# magnetorquer_board.net
KiCad netlist of a schematic drawn in EAGLE
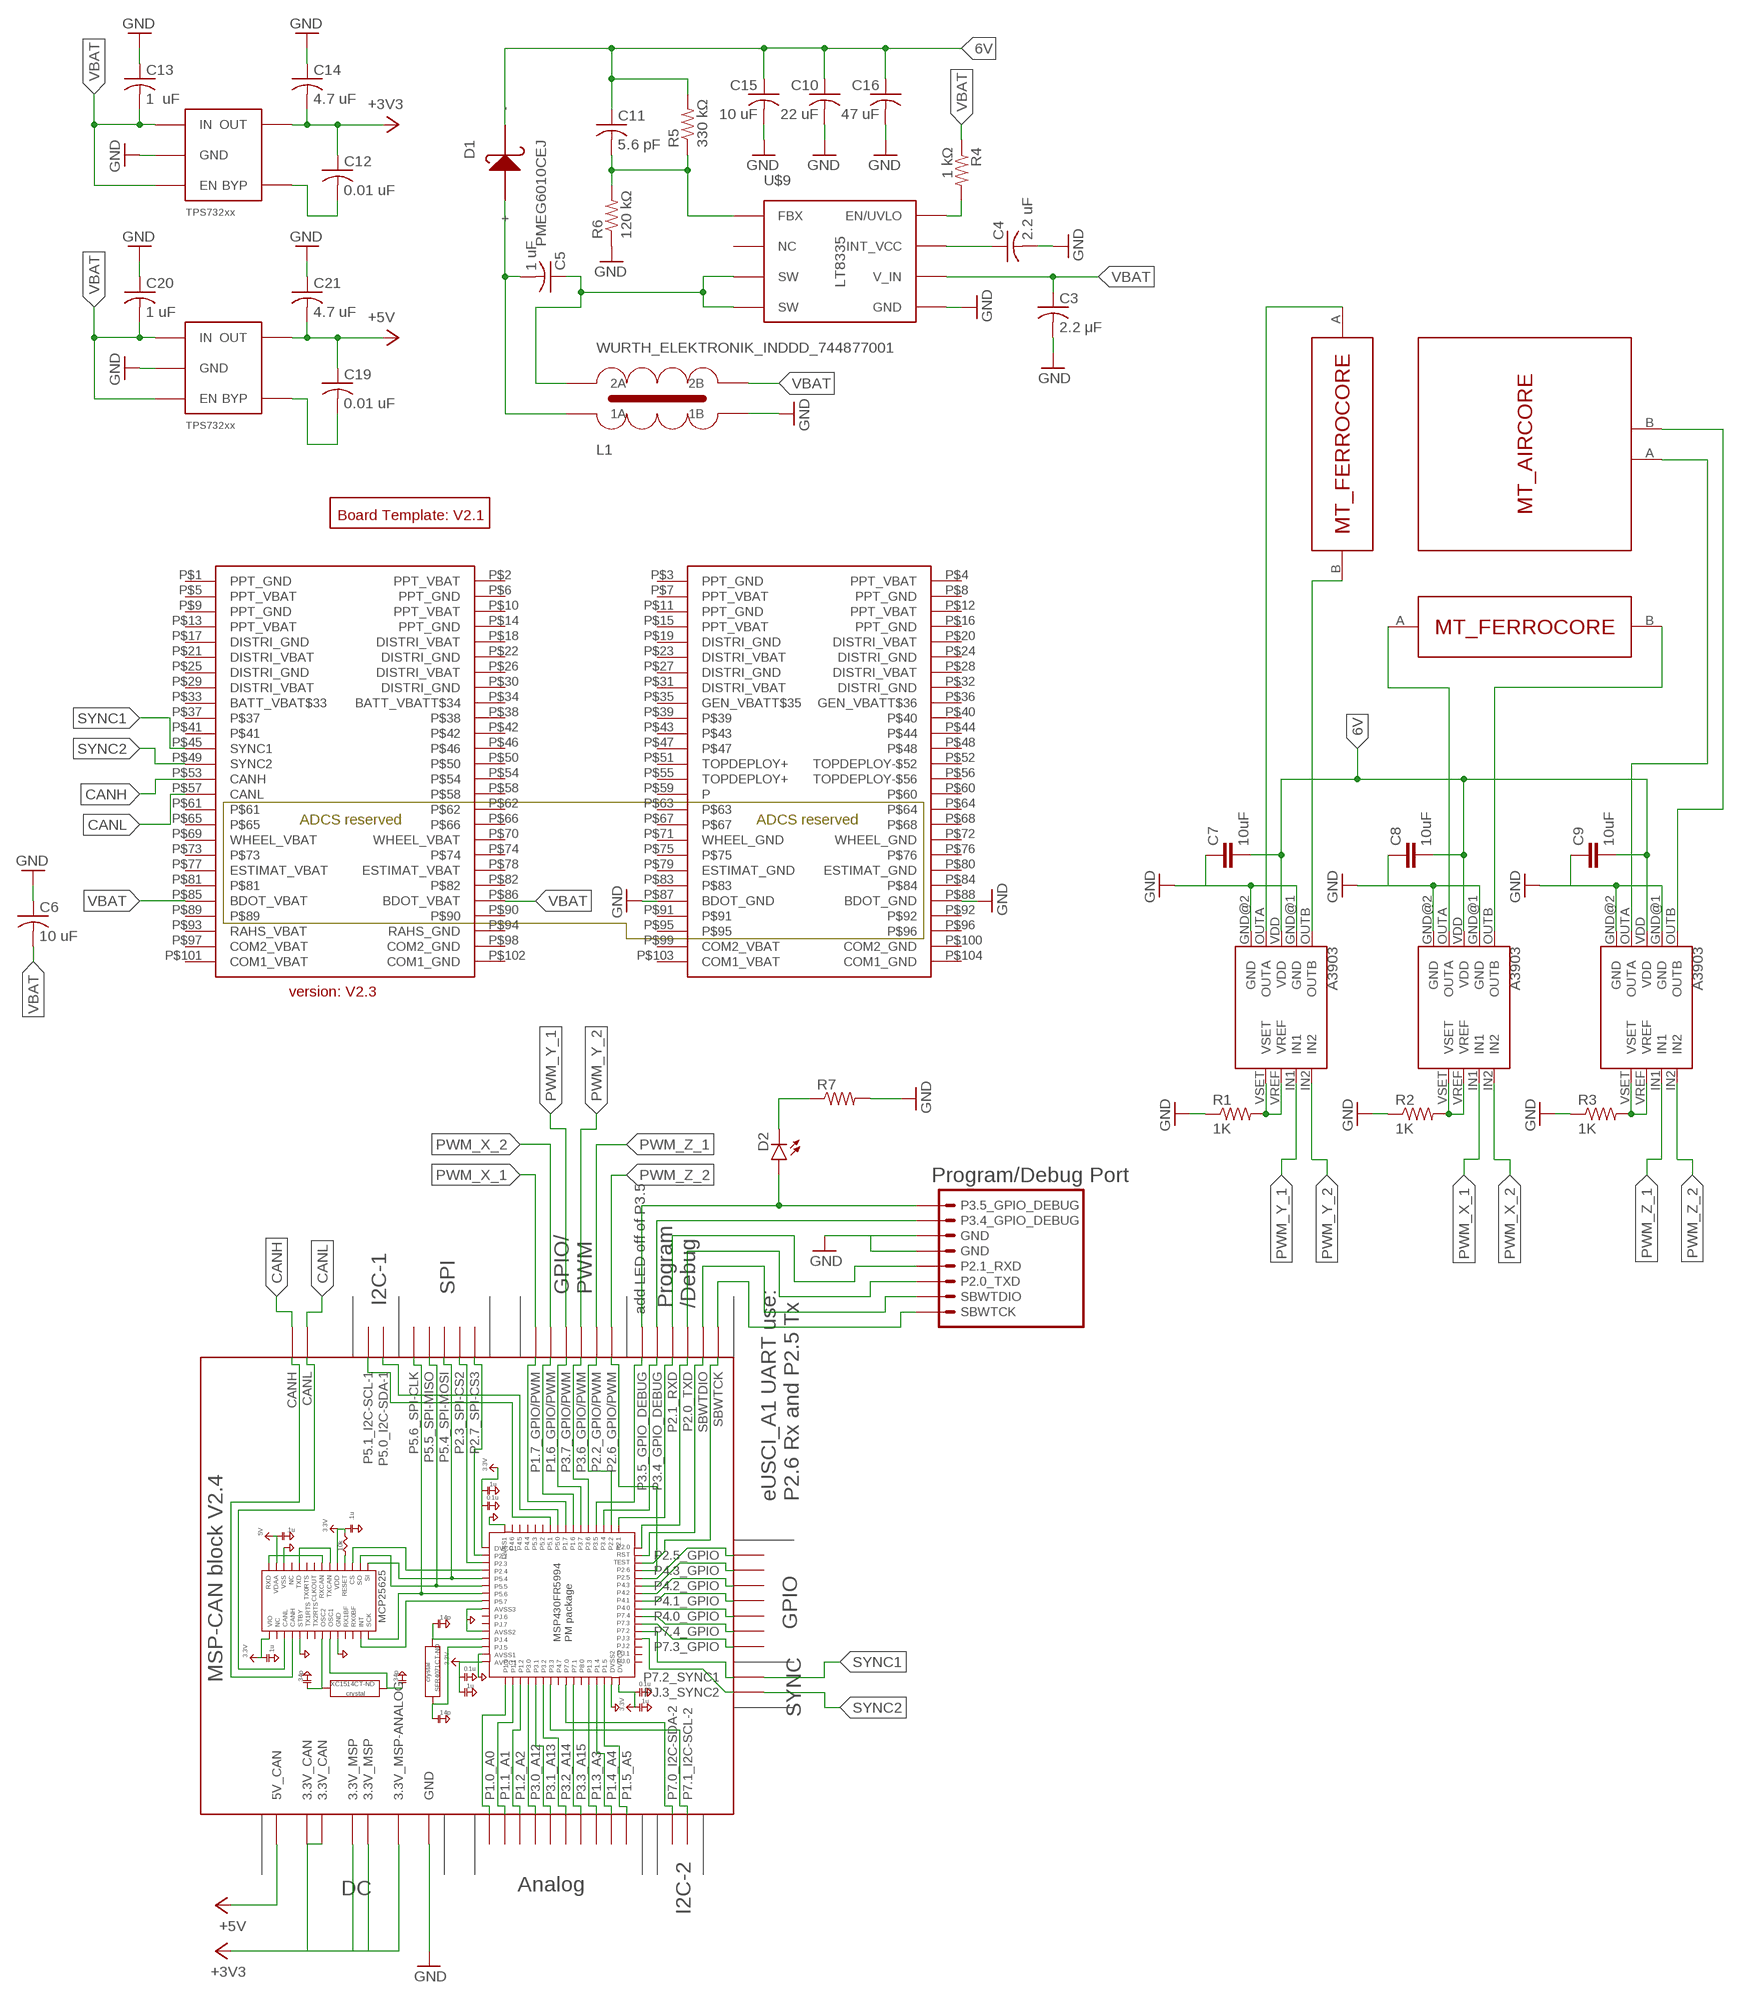
[diagram p0: schematic, sheet 1]

(export (version "E")
  (design (tool "Eeschema 10.0.6"))
  (components
    (comp (ref "C3")
      (value "2.2 μF")
      (footprint "eagle-import:C0805")
      (libsource (lib "eagle-import") (part "C-USC0805"))
    )
    (comp (ref "C4")
      (value "2.2 uF")
      (footprint "eagle-import:C0805")
      (libsource (lib "eagle-import") (part "C-USC0805"))
    )
    (comp (ref "C5")
      (value "1 uF")
      (footprint "eagle-import:C0805")
      (libsource (lib "eagle-import") (part "C-USC0805"))
    )
    (comp (ref "C6")
      (value "10 uF")
      (footprint "eagle-import:C0805")
      (libsource (lib "eagle-import") (part "C-USC0805"))
    )
    (comp (ref "C7")
      (value "10uF")
      (footprint "eagle-import:C0805")
      (libsource (lib "eagle-import") (part "C-EUC0805"))
    )
    (comp (ref "C8")
      (value "10uF")
      (footprint "eagle-import:C0805")
      (libsource (lib "eagle-import") (part "C-EUC0805"))
    )
    (comp (ref "C9")
      (value "10uF")
      (footprint "eagle-import:C0805")
      (libsource (lib "eagle-import") (part "C-EUC0805"))
    )
    (comp (ref "C10")
      (value "22 uF")
      (footprint "eagle-import:C1206")
      (libsource (lib "eagle-import") (part "C-USC1206"))
    )
    (comp (ref "C11")
      (value "5.6 pF")
      (footprint "eagle-import:C0805")
      (libsource (lib "eagle-import") (part "C-USC0805"))
    )
    (comp (ref "C12")
      (value "0.01 uF")
      (footprint "eagle-import:C0805")
      (libsource (lib "eagle-import") (part "C-USC0805"))
    )
    (comp (ref "C13")
      (value "1 uF")
      (footprint "eagle-import:C0805")
      (libsource (lib "eagle-import") (part "C-USC0805"))
    )
    (comp (ref "C14")
      (value "4.7 uF")
      (footprint "eagle-import:C0805")
      (libsource (lib "eagle-import") (part "C-USC0805"))
    )
    (comp (ref "C15")
      (value "10 uF")
      (footprint "eagle-import:C0805")
      (libsource (lib "eagle-import") (part "C-USC0805"))
    )
    (comp (ref "C16")
      (value "47 uF")
      (footprint "eagle-import:C1206")
      (libsource (lib "eagle-import") (part "C-USC1206"))
    )
    (comp (ref "C19")
      (value "0.01 uF")
      (footprint "eagle-import:C0805")
      (libsource (lib "eagle-import") (part "C-USC0805"))
    )
    (comp (ref "C20")
      (value "1 uF")
      (footprint "eagle-import:C0805")
      (libsource (lib "eagle-import") (part "C-USC0805"))
    )
    (comp (ref "C21")
      (value "4.7 uF")
      (footprint "eagle-import:C0805")
      (libsource (lib "eagle-import") (part "C-USC0805"))
    )
    (comp (ref "D1")
      (value "PMEG6010CEJ")
      (footprint "eagle-import:SC-90")
      (libsource (lib "eagle-import") (part "PMEG6010CEJ"))
    )
    (comp (ref "D2")
      (value "LED")
      (footprint "eagle-import:LED-1206")
      (libsource (lib "eagle-import") (part "LED"))
    )
    (comp (ref "L1")
      (value "WURTH_ELEKTRONIK_INDDD_744877001")
      (footprint "eagle-import:WURTH_ELEKTRONIK_INDDD_744877001")
      (libsource (lib "eagle-import") (part "WURTH_ELEKTRONIK_INDDD_744877001"))
    )
    (comp (ref "LDO_3V1")
      (value "TPS732XX")
      (footprint "eagle-import:SOT-23-5")
      (libsource (lib "eagle-import") (part "TPS732XX"))
    )
    (comp (ref "LDO_5V1")
      (value "TPS732XX")
      (footprint "eagle-import:SOT-23-5")
      (libsource (lib "eagle-import") (part "TPS732XX"))
    )
    (comp (ref "R1")
      (value "1K")
      (footprint "eagle-import:R0603")
      (libsource (lib "eagle-import") (part "R-US_R0603"))
    )
    (comp (ref "R2")
      (value "1K")
      (footprint "eagle-import:R0603")
      (libsource (lib "eagle-import") (part "R-US_R0603"))
    )
    (comp (ref "R3")
      (value "1K")
      (footprint "eagle-import:R0603")
      (libsource (lib "eagle-import") (part "R-US_R0603"))
    )
    (comp (ref "R4")
      (value "1 kΩ")
      (footprint "eagle-import:0805")
      (libsource (lib "eagle-import") (part "RESISTOR0805"))
    )
    (comp (ref "R5")
      (value "330 kΩ")
      (footprint "eagle-import:0805")
      (libsource (lib "eagle-import") (part "RESISTOR0805"))
    )
    (comp (ref "R6")
      (value "120 kΩ")
      (footprint "eagle-import:0805")
      (libsource (lib "eagle-import") (part "RESISTOR0805"))
    )
    (comp (ref "R7")
      (value "RESISTOR0805")
      (footprint "eagle-import:0805")
      (libsource (lib "eagle-import") (part "RESISTOR0805"))
    )
    (comp (ref "U$1")
      (value "PC104_CONNECTOR")
      (footprint "eagle-import:PC104_CONNECTOR")
      (libsource (lib "eagle-import") (part "PC104_CONNECTOR"))
    )
    (comp (ref "U$2")
      (value "BOARD_TEMPLATE1")
      (footprint "eagle-import:BOARD_TEMPLATE")
      (libsource (lib "eagle-import") (part "BOARD_TEMPLATE1"))
    )
    (comp (ref "U$3")
      (value "MT_AIRCORE")
      (footprint "eagle-import:MT_AIRCORE")
      (libsource (lib "eagle-import") (part "MT_AIRCORE"))
    )
    (comp (ref "U$4")
      (value "MT_FERROCORE")
      (footprint "eagle-import:MT_FERROCORE")
      (libsource (lib "eagle-import") (part "MT_FERROCORE"))
    )
    (comp (ref "U$5")
      (value "MT_FERROCORE")
      (footprint "eagle-import:MT_FERROCORE")
      (libsource (lib "eagle-import") (part "MT_FERROCORE"))
    )
    (comp (ref "U$7")
      (value "MSP-CAN_BLOCK")
      (footprint "eagle-import:MSP-CAN_BLOCK")
      (libsource (lib "eagle-import") (part "MSP-CAN_BLOCK"))
    )
    (comp (ref "U$8")
      (value "PROGRAM/DEBUG_PORT")
      (footprint "eagle-import:1X08_CONNECTOR")
      (libsource (lib "eagle-import") (part "PROGRAM/DEBUG_PORT"))
    )
    (comp (ref "U$9")
      (value "LT8335")
      (footprint "eagle-import:DDB")
      (libsource (lib "eagle-import") (part "LT8335"))
    )
    (comp (ref "U1")
      (value "A3903")
      (footprint "eagle-import:DFN-8EE")
      (libsource (lib "eagle-import") (part "A3903"))
    )
    (comp (ref "U2")
      (value "A3903")
      (footprint "eagle-import:DFN-8EE")
      (libsource (lib "eagle-import") (part "A3903"))
    )
    (comp (ref "U3")
      (value "A3903")
      (footprint "eagle-import:DFN-8EE")
      (libsource (lib "eagle-import") (part "A3903"))
    )
  )
  (nets
    (net (code "1") (name "+3V3") (class "Default")
      (node (ref "C12") (pin "1") (pinfunction "1_1") (pintype "passive"))
      (node (ref "C14") (pin "2") (pinfunction "2_2") (pintype "passive"))
      (node (ref "LDO_3V1") (pin "P$5") (pinfunction "OUT_P$5") (pintype "bidirectional"))
      (node (ref "U$7") (pin "3.3V@CAN1") (pinfunction "3.3V_CAN_3.3V@CAN1") (pintype "bidirectional"))
      (node (ref "U$7") (pin "3.3V@CAN2") (pinfunction "3.3V_CAN_3.3V@CAN2") (pintype "bidirectional"))
      (node (ref "U$7") (pin "3.3V@MSP1") (pinfunction "3.3V_MSP_3.3V@MSP1") (pintype "bidirectional"))
      (node (ref "U$7") (pin "3.3V@MSP2") (pinfunction "3.3V_MSP_3.3V@MSP2") (pintype "bidirectional"))
      (node (ref "U$7") (pin "3.3V_ANALOG@MSP2") (pinfunction "3.3V_MSP-ANALOG_3.3V_ANALOG@MSP2") (pintype "bidirectional"))
    )
    (net (code "2") (name "+5V") (class "Default")
      (node (ref "C19") (pin "1") (pinfunction "1_1") (pintype "passive"))
      (node (ref "C21") (pin "2") (pinfunction "2_2") (pintype "passive"))
      (node (ref "LDO_5V1") (pin "P$5") (pinfunction "OUT_P$5") (pintype "bidirectional"))
      (node (ref "U$7") (pin "5V") (pinfunction "5V_CAN_5V") (pintype "bidirectional"))
    )
    (net (code "3") (name "6V") (class "Default")
      (node (ref "C10") (pin "1") (pinfunction "1_1") (pintype "passive"))
      (node (ref "C11") (pin "1") (pinfunction "1_1") (pintype "passive"))
      (node (ref "C15") (pin "1") (pinfunction "1_1") (pintype "passive"))
      (node (ref "C16") (pin "1") (pinfunction "1_1") (pintype "passive"))
      (node (ref "C7") (pin "2") (pinfunction "2_2") (pintype "passive"))
      (node (ref "C8") (pin "2") (pinfunction "2_2") (pintype "passive"))
      (node (ref "C9") (pin "2") (pinfunction "2_2") (pintype "passive"))
      (node (ref "D1") (pin "P$2") (pinfunction "-_P$2") (pintype "bidirectional"))
      (node (ref "R5") (pin "2") (pinfunction "2_2") (pintype "passive"))
      (node (ref "U1") (pin "VDD") (pinfunction "VDD_VDD") (pintype "power_in"))
      (node (ref "U2") (pin "VDD") (pinfunction "VDD_VDD") (pintype "power_in"))
      (node (ref "U3") (pin "VDD") (pinfunction "VDD_VDD") (pintype "power_in"))
    )
    (net (code "4") (name "CANH") (class "Default")
      (node (ref "U$1") (pin "P$53") (pinfunction "CANH_P$53") (pintype "bidirectional"))
      (node (ref "U$7") (pin "CANH") (pinfunction "CANH_CANH") (pintype "bidirectional"))
    )
    (net (code "5") (name "CANL") (class "Default")
      (node (ref "U$1") (pin "P$57") (pinfunction "CANL_P$57") (pintype "bidirectional"))
      (node (ref "U$7") (pin "CANL") (pinfunction "CANL_CANL") (pintype "bidirectional"))
    )
    (net (code "6") (name "GND") (class "Default")
      (node (ref "C10") (pin "2") (pinfunction "2_2") (pintype "passive"))
      (node (ref "C13") (pin "1") (pinfunction "1_1") (pintype "passive"))
      (node (ref "C14") (pin "1") (pinfunction "1_1") (pintype "passive"))
      (node (ref "C15") (pin "2") (pinfunction "2_2") (pintype "passive"))
      (node (ref "C16") (pin "2") (pinfunction "2_2") (pintype "passive"))
      (node (ref "C20") (pin "1") (pinfunction "1_1") (pintype "passive"))
      (node (ref "C21") (pin "1") (pinfunction "1_1") (pintype "passive"))
      (node (ref "C3") (pin "2") (pinfunction "2_2") (pintype "passive"))
      (node (ref "C4") (pin "2") (pinfunction "2_2") (pintype "passive"))
      (node (ref "C6") (pin "1") (pinfunction "1_1") (pintype "passive"))
      (node (ref "C7") (pin "1") (pinfunction "1_1") (pintype "passive"))
      (node (ref "C8") (pin "1") (pinfunction "1_1") (pintype "passive"))
      (node (ref "C9") (pin "1") (pinfunction "1_1") (pintype "passive"))
      (node (ref "L1") (pin "P$2") (pinfunction "1B_P$2") (pintype "bidirectional"))
      (node (ref "LDO_3V1") (pin "P$2") (pinfunction "GND_P$2") (pintype "bidirectional"))
      (node (ref "LDO_5V1") (pin "P$2") (pinfunction "GND_P$2") (pintype "bidirectional"))
      (node (ref "R1") (pin "1") (pinfunction "1_1") (pintype "passive"))
      (node (ref "R2") (pin "1") (pinfunction "1_1") (pintype "passive"))
      (node (ref "R3") (pin "1") (pinfunction "1_1") (pintype "passive"))
      (node (ref "R6") (pin "1") (pinfunction "1_1") (pintype "passive"))
      (node (ref "R7") (pin "2") (pinfunction "2_2") (pintype "passive"))
      (node (ref "U$1") (pin "P$87") (pinfunction "BDOT_GND_P$87") (pintype "bidirectional"))
      (node (ref "U$1") (pin "P$88") (pinfunction "BDOT_GND_P$88") (pintype "bidirectional"))
      (node (ref "U$7") (pin "GND@1") (pinfunction "GND_GND@1") (pintype "bidirectional"))
      (node (ref "U$7") (pin "GND@10") (pinfunction "GND_GND@10") (pintype "bidirectional"))
      (node (ref "U$7") (pin "GND@11") (pinfunction "GND_GND@11") (pintype "bidirectional"))
      (node (ref "U$7") (pin "GND@12") (pinfunction "GND_GND@12") (pintype "bidirectional"))
      (node (ref "U$7") (pin "GND@13") (pinfunction "GND_GND@13") (pintype "bidirectional"))
      (node (ref "U$7") (pin "GND@14") (pinfunction "GND_GND@14") (pintype "bidirectional"))
      (node (ref "U$7") (pin "GND@15") (pinfunction "GND_GND@15") (pintype "bidirectional"))
      (node (ref "U$7") (pin "GND@16") (pinfunction "GND_GND@16") (pintype "bidirectional"))
      (node (ref "U$7") (pin "GND@17") (pinfunction "GND_GND@17") (pintype "bidirectional"))
      (node (ref "U$7") (pin "GND@2") (pinfunction "GND_GND@2") (pintype "bidirectional"))
      (node (ref "U$7") (pin "GND@26") (pinfunction "GND_GND@26") (pintype "bidirectional"))
      (node (ref "U$7") (pin "GND@3") (pinfunction "GND_GND@3") (pintype "bidirectional"))
      (node (ref "U$7") (pin "GND@4") (pinfunction "GND_GND@4") (pintype "bidirectional"))
      (node (ref "U$7") (pin "GND@5") (pinfunction "GND_GND@5") (pintype "bidirectional"))
      (node (ref "U$7") (pin "GND@7") (pinfunction "GND_GND@7") (pintype "bidirectional"))
      (node (ref "U$7") (pin "GND@8") (pinfunction "GND_GND@8") (pintype "bidirectional"))
      (node (ref "U$7") (pin "GND@9") (pinfunction "GND_GND@9") (pintype "bidirectional"))
      (node (ref "U$8") (pin "5") (pinfunction "GND_5") (pintype "bidirectional"))
      (node (ref "U$8") (pin "6") (pinfunction "GND_6") (pintype "bidirectional"))
      (node (ref "U$9") (pin "GND") (pinfunction "GND_GND") (pintype "bidirectional"))
      (node (ref "U$9") (pin "P$5") (pinfunction "GND_P$5") (pintype "bidirectional"))
      (node (ref "U1") (pin "GND@1") (pinfunction "GND_GND@1") (pintype "power_in"))
      (node (ref "U1") (pin "GND@2") (pinfunction "GND_GND@2") (pintype "power_in"))
      (node (ref "U2") (pin "GND@1") (pinfunction "GND_GND@1") (pintype "power_in"))
      (node (ref "U2") (pin "GND@2") (pinfunction "GND_GND@2") (pintype "power_in"))
      (node (ref "U3") (pin "GND@1") (pinfunction "GND_GND@1") (pintype "power_in"))
      (node (ref "U3") (pin "GND@2") (pinfunction "GND_GND@2") (pintype "power_in"))
    )
    (net (code "7") (name "Net-(D1-+)") (class "Default")
      (node (ref "C5") (pin "2") (pinfunction "2_2") (pintype "passive"))
      (node (ref "D1") (pin "P$1") (pinfunction "+_P$1") (pintype "bidirectional"))
      (node (ref "L1") (pin "P$1") (pinfunction "1A_P$1") (pintype "bidirectional"))
    )
    (net (code "8") (name "Net-(D2-PadC)") (class "Default")
      (node (ref "D2") (pin "C") (pinfunction "C_C") (pintype "passive"))
      (node (ref "R7") (pin "1") (pinfunction "1_1") (pintype "passive"))
    )
    (net (code "9") (name "Net-(L1-2A)") (class "Default")
      (node (ref "C5") (pin "1") (pinfunction "1_1") (pintype "passive"))
      (node (ref "L1") (pin "P$3") (pinfunction "2A_P$3") (pintype "bidirectional"))
      (node (ref "U$9") (pin "P$3") (pinfunction "SW_P$3") (pintype "bidirectional"))
      (node (ref "U$9") (pin "P$4") (pinfunction "SW_P$4") (pintype "bidirectional"))
    )
    (net (code "10") (name "Net-(LDO_3V1-BYP)") (class "Default")
      (node (ref "C12") (pin "2") (pinfunction "2_2") (pintype "passive"))
      (node (ref "LDO_3V1") (pin "P$4") (pinfunction "BYP_P$4") (pintype "bidirectional"))
    )
    (net (code "11") (name "Net-(LDO_5V1-BYP)") (class "Default")
      (node (ref "C19") (pin "2") (pinfunction "2_2") (pintype "passive"))
      (node (ref "LDO_5V1") (pin "P$4") (pinfunction "BYP_P$4") (pintype "bidirectional"))
    )
    (net (code "12") (name "Net-(R1-Pad2)") (class "Default")
      (node (ref "R1") (pin "2") (pinfunction "2_2") (pintype "passive"))
      (node (ref "U1") (pin "VREF") (pinfunction "VREF_VREF") (pintype "power_in"))
      (node (ref "U1") (pin "VSET") (pinfunction "VSET_VSET") (pintype "bidirectional"))
    )
    (net (code "13") (name "Net-(R2-Pad2)") (class "Default")
      (node (ref "R2") (pin "2") (pinfunction "2_2") (pintype "passive"))
      (node (ref "U2") (pin "VREF") (pinfunction "VREF_VREF") (pintype "power_in"))
      (node (ref "U2") (pin "VSET") (pinfunction "VSET_VSET") (pintype "bidirectional"))
    )
    (net (code "14") (name "Net-(R3-Pad2)") (class "Default")
      (node (ref "R3") (pin "2") (pinfunction "2_2") (pintype "passive"))
      (node (ref "U3") (pin "VREF") (pinfunction "VREF_VREF") (pintype "power_in"))
      (node (ref "U3") (pin "VSET") (pinfunction "VSET_VSET") (pintype "bidirectional"))
    )
    (net (code "15") (name "Net-(U$3-PadA)") (class "Default")
      (node (ref "U$3") (pin "A") (pinfunction "A_A") (pintype "bidirectional"))
      (node (ref "U3") (pin "OUTA") (pinfunction "OUTA_OUTA") (pintype "output"))
    )
    (net (code "16") (name "Net-(U$3-PadB)") (class "Default")
      (node (ref "U$3") (pin "B") (pinfunction "B_B") (pintype "bidirectional"))
      (node (ref "U3") (pin "OUTB") (pinfunction "OUTB_OUTB") (pintype "output"))
    )
    (net (code "17") (name "Net-(U$4-PadA)") (class "Default")
      (node (ref "U$4") (pin "A") (pinfunction "A_A") (pintype "bidirectional"))
      (node (ref "U1") (pin "OUTA") (pinfunction "OUTA_OUTA") (pintype "output"))
    )
    (net (code "18") (name "Net-(U$4-PadB)") (class "Default")
      (node (ref "U$4") (pin "B") (pinfunction "B_B") (pintype "bidirectional"))
      (node (ref "U1") (pin "OUTB") (pinfunction "OUTB_OUTB") (pintype "output"))
    )
    (net (code "19") (name "Net-(U$5-PadA)") (class "Default")
      (node (ref "U$5") (pin "A") (pinfunction "A_A") (pintype "bidirectional"))
      (node (ref "U2") (pin "OUTA") (pinfunction "OUTA_OUTA") (pintype "output"))
    )
    (net (code "20") (name "Net-(U$5-PadB)") (class "Default")
      (node (ref "U$5") (pin "B") (pinfunction "B_B") (pintype "bidirectional"))
      (node (ref "U2") (pin "OUTB") (pinfunction "OUTB_OUTB") (pintype "output"))
    )
    (net (code "21") (name "Net-(U$7-PadSBWTCK)") (class "Default")
      (node (ref "U$7") (pin "SBWTCK") (pinfunction "SBWTCK_SBWTCK") (pintype "bidirectional"))
      (node (ref "U$8") (pin "SBWTCK") (pinfunction "SBWTCK_SBWTCK") (pintype "bidirectional"))
    )
    (net (code "22") (name "Net-(U$8-P2.0_TXD)") (class "Default")
      (node (ref "U$7") (pin "P2.0_TXD") (pinfunction "P2.0_TXD_P2.0_TXD") (pintype "bidirectional"))
      (node (ref "U$8") (pin "3") (pinfunction "P2.0_TXD_3") (pintype "bidirectional"))
    )
    (net (code "23") (name "Net-(U$8-P2.1_RXD)") (class "Default")
      (node (ref "U$7") (pin "P2.1_RXD") (pinfunction "P2.1_RXD_P2.1_RXD") (pintype "bidirectional"))
      (node (ref "U$8") (pin "4") (pinfunction "P2.1_RXD_4") (pintype "bidirectional"))
    )
    (net (code "24") (name "Net-(U$8-P3.4_GPIO_DEBUG)") (class "Default")
      (node (ref "U$7") (pin "P3.4_GPIO_DEBUG") (pinfunction "P3.4_GPIO_DEBUG_P3.4_GPIO_DEBUG") (pintype "bidirectional"))
      (node (ref "U$8") (pin "7") (pinfunction "P3.4_GPIO_DEBUG_7") (pintype "bidirectional"))
    )
    (net (code "25") (name "Net-(U$8-P3.5_GPIO_DEBUG)") (class "Default")
      (node (ref "D2") (pin "A") (pinfunction "A_A") (pintype "passive"))
      (node (ref "U$7") (pin "P3.5_GPIO_DEBUG") (pinfunction "P3.5_GPIO_DEBUG_P3.5_GPIO_DEBUG") (pintype "bidirectional"))
      (node (ref "U$8") (pin "8") (pinfunction "P3.5_GPIO_DEBUG_8") (pintype "bidirectional"))
    )
    (net (code "26") (name "Net-(U$8-SBWTDIO)") (class "Default")
      (node (ref "U$7") (pin "SBWTDIO") (pinfunction "SBWTDIO_SBWTDIO") (pintype "bidirectional"))
      (node (ref "U$8") (pin "2") (pinfunction "SBWTDIO_2") (pintype "bidirectional"))
    )
    (net (code "27") (name "Net-(U$9-EN{slash}UVLO)") (class "Default")
      (node (ref "R4") (pin "2") (pinfunction "2_2") (pintype "passive"))
      (node (ref "U$9") (pin "P$8") (pinfunction "EN/UVLO_P$8") (pintype "bidirectional"))
    )
    (net (code "28") (name "Net-(U$9-FBX)") (class "Default")
      (node (ref "C11") (pin "2") (pinfunction "2_2") (pintype "passive"))
      (node (ref "R5") (pin "1") (pinfunction "1_1") (pintype "passive"))
      (node (ref "R6") (pin "2") (pinfunction "2_2") (pintype "passive"))
      (node (ref "U$9") (pin "P$1") (pinfunction "FBX_P$1") (pintype "bidirectional"))
    )
    (net (code "29") (name "Net-(U$9-INT_VCC)") (class "Default")
      (node (ref "C4") (pin "1") (pinfunction "1_1") (pintype "passive"))
      (node (ref "U$9") (pin "P$7") (pinfunction "INT_VCC_P$7") (pintype "bidirectional"))
    )
    (net (code "30") (name "PWM_X_1") (class "Default")
      (node (ref "U$7") (pin "P1.7_GPIO/PWM") (pinfunction "P1.7_GPIO/PWM_P1.7_GPIO/PWM") (pintype "bidirectional"))
      (node (ref "U2") (pin "IN1") (pinfunction "IN1_IN1") (pintype "input"))
    )
    (net (code "31") (name "PWM_X_2") (class "Default")
      (node (ref "U$7") (pin "P1.6_GPIO/PWM") (pinfunction "P1.6_GPIO/PWM_P1.6_GPIO/PWM") (pintype "bidirectional"))
      (node (ref "U2") (pin "IN2") (pinfunction "IN2_IN2") (pintype "input"))
    )
    (net (code "32") (name "PWM_Y_1") (class "Default")
      (node (ref "U$7") (pin "P3.7_GPIO/PWM") (pinfunction "P3.7_GPIO/PWM_P3.7_GPIO/PWM") (pintype "bidirectional"))
      (node (ref "U1") (pin "IN1") (pinfunction "IN1_IN1") (pintype "input"))
    )
    (net (code "33") (name "PWM_Y_2") (class "Default")
      (node (ref "U$7") (pin "P3.6_GPIO/PWM") (pinfunction "P3.6_GPIO/PWM_P3.6_GPIO/PWM") (pintype "bidirectional"))
      (node (ref "U1") (pin "IN2") (pinfunction "IN2_IN2") (pintype "input"))
    )
    (net (code "34") (name "PWM_Z_1") (class "Default")
      (node (ref "U$7") (pin "P2.2_GPIO/PWM") (pinfunction "P2.2_GPIO/PWM_P2.2_GPIO/PWM") (pintype "bidirectional"))
      (node (ref "U3") (pin "IN1") (pinfunction "IN1_IN1") (pintype "input"))
    )
    (net (code "35") (name "PWM_Z_2") (class "Default")
      (node (ref "U$7") (pin "P2.6_GPIO/PWM") (pinfunction "P2.6_GPIO/PWM_P2.6_GPIO/PWM") (pintype "bidirectional"))
      (node (ref "U3") (pin "IN2") (pinfunction "IN2_IN2") (pintype "input"))
    )
    (net (code "36") (name "SYNC1") (class "Default")
      (node (ref "U$1") (pin "P$45") (pinfunction "SYNC1_P$45") (pintype "bidirectional"))
      (node (ref "U$7") (pin "P7.2_SYNC1") (pinfunction "P7.2_SYNC1_P7.2_SYNC1") (pintype "bidirectional"))
    )
    (net (code "37") (name "SYNC2") (class "Default")
      (node (ref "U$1") (pin "P$49") (pinfunction "SYNC2_P$49") (pintype "bidirectional"))
      (node (ref "U$7") (pin "PJ.3_SYNC2") (pinfunction "PJ.3_SYNC2_PJ.3_SYNC2") (pintype "bidirectional"))
    )
    (net (code "38") (name "VBAT") (class "Default")
      (node (ref "C13") (pin "2") (pinfunction "2_2") (pintype "passive"))
      (node (ref "C20") (pin "2") (pinfunction "2_2") (pintype "passive"))
      (node (ref "C3") (pin "1") (pinfunction "1_1") (pintype "passive"))
      (node (ref "C6") (pin "2") (pinfunction "2_2") (pintype "passive"))
      (node (ref "L1") (pin "P$4") (pinfunction "2B_P$4") (pintype "bidirectional"))
      (node (ref "LDO_3V1") (pin "P$1") (pinfunction "IN_P$1") (pintype "bidirectional"))
      (node (ref "LDO_3V1") (pin "P$3") (pinfunction "EN_P$3") (pintype "bidirectional"))
      (node (ref "LDO_5V1") (pin "P$1") (pinfunction "IN_P$1") (pintype "bidirectional"))
      (node (ref "LDO_5V1") (pin "P$3") (pinfunction "EN_P$3") (pintype "bidirectional"))
      (node (ref "R4") (pin "1") (pinfunction "1_1") (pintype "passive"))
      (node (ref "U$1") (pin "P$85") (pinfunction "BDOT_VBAT_P$85") (pintype "bidirectional"))
      (node (ref "U$1") (pin "P$86") (pinfunction "BDOT_VBAT_P$86") (pintype "bidirectional"))
      (node (ref "U$9") (pin "P$6") (pinfunction "V_IN_P$6") (pintype "bidirectional"))
    )
    (net (code "39") (name "unconnected-(U$1-BATT_VBAT$33-PadP$33)") (class "Default")
      (node (ref "U$1") (pin "P$33") (pinfunction "BATT_VBAT$33_P$33") (pintype "bidirectional"))
    )
    (net (code "40") (name "unconnected-(U$1-BATT_VBATT$34-PadP$34)") (class "Default")
      (node (ref "U$1") (pin "P$34") (pinfunction "BATT_VBATT$34_P$34") (pintype "bidirectional"))
    )
    (net (code "41") (name "unconnected-(U$1-COM1_GND-PadP$102)") (class "Default")
      (node (ref "U$1") (pin "P$102") (pinfunction "COM1_GND_P$102") (pintype "bidirectional"))
    )
    (net (code "42") (name "unconnected-(U$1-COM1_GND-PadP$104)") (class "Default")
      (node (ref "U$1") (pin "P$104") (pinfunction "COM1_GND_P$104") (pintype "bidirectional"))
    )
    (net (code "43") (name "unconnected-(U$1-COM1_VBAT-PadP$101)") (class "Default")
      (node (ref "U$1") (pin "P$101") (pinfunction "COM1_VBAT_P$101") (pintype "bidirectional"))
    )
    (net (code "44") (name "unconnected-(U$1-COM1_VBAT-PadP$103)") (class "Default")
      (node (ref "U$1") (pin "P$103") (pinfunction "COM1_VBAT_P$103") (pintype "bidirectional"))
    )
    (net (code "45") (name "unconnected-(U$1-COM2_GND-PadP$98)") (class "Default")
      (node (ref "U$1") (pin "P$98") (pinfunction "COM2_GND_P$98") (pintype "bidirectional"))
    )
    (net (code "46") (name "unconnected-(U$1-COM2_GND-PadP$100)") (class "Default")
      (node (ref "U$1") (pin "P$100") (pinfunction "COM2_GND_P$100") (pintype "bidirectional"))
    )
    (net (code "47") (name "unconnected-(U$1-COM2_VBAT-PadP$97)") (class "Default")
      (node (ref "U$1") (pin "P$97") (pinfunction "COM2_VBAT_P$97") (pintype "bidirectional"))
    )
    (net (code "48") (name "unconnected-(U$1-COM2_VBAT-PadP$99)") (class "Default")
      (node (ref "U$1") (pin "P$99") (pinfunction "COM2_VBAT_P$99") (pintype "bidirectional"))
    )
    (net (code "49") (name "unconnected-(U$1-DISTRI_GND-PadP$17)") (class "Default")
      (node (ref "U$1") (pin "P$17") (pinfunction "DISTRI_GND_P$17") (pintype "bidirectional"))
    )
    (net (code "50") (name "unconnected-(U$1-DISTRI_GND-PadP$19)") (class "Default")
      (node (ref "U$1") (pin "P$19") (pinfunction "DISTRI_GND_P$19") (pintype "bidirectional"))
    )
    (net (code "51") (name "unconnected-(U$1-DISTRI_GND-PadP$22)") (class "Default")
      (node (ref "U$1") (pin "P$22") (pinfunction "DISTRI_GND_P$22") (pintype "bidirectional"))
    )
    (net (code "52") (name "unconnected-(U$1-DISTRI_GND-PadP$24)") (class "Default")
      (node (ref "U$1") (pin "P$24") (pinfunction "DISTRI_GND_P$24") (pintype "bidirectional"))
    )
    (net (code "53") (name "unconnected-(U$1-DISTRI_GND-PadP$25)") (class "Default")
      (node (ref "U$1") (pin "P$25") (pinfunction "DISTRI_GND_P$25") (pintype "bidirectional"))
    )
    (net (code "54") (name "unconnected-(U$1-DISTRI_GND-PadP$27)") (class "Default")
      (node (ref "U$1") (pin "P$27") (pinfunction "DISTRI_GND_P$27") (pintype "bidirectional"))
    )
    (net (code "55") (name "unconnected-(U$1-DISTRI_GND-PadP$30)") (class "Default")
      (node (ref "U$1") (pin "P$30") (pinfunction "DISTRI_GND_P$30") (pintype "bidirectional"))
    )
    (net (code "56") (name "unconnected-(U$1-DISTRI_GND-PadP$32)") (class "Default")
      (node (ref "U$1") (pin "P$32") (pinfunction "DISTRI_GND_P$32") (pintype "bidirectional"))
    )
    (net (code "57") (name "unconnected-(U$1-DISTRI_VBAT-PadP$18)") (class "Default")
      (node (ref "U$1") (pin "P$18") (pinfunction "DISTRI_VBAT_P$18") (pintype "bidirectional"))
    )
    (net (code "58") (name "unconnected-(U$1-DISTRI_VBAT-PadP$20)") (class "Default")
      (node (ref "U$1") (pin "P$20") (pinfunction "DISTRI_VBAT_P$20") (pintype "bidirectional"))
    )
    (net (code "59") (name "unconnected-(U$1-DISTRI_VBAT-PadP$21)") (class "Default")
      (node (ref "U$1") (pin "P$21") (pinfunction "DISTRI_VBAT_P$21") (pintype "bidirectional"))
    )
    (net (code "60") (name "unconnected-(U$1-DISTRI_VBAT-PadP$23)") (class "Default")
      (node (ref "U$1") (pin "P$23") (pinfunction "DISTRI_VBAT_P$23") (pintype "bidirectional"))
    )
    (net (code "61") (name "unconnected-(U$1-DISTRI_VBAT-PadP$26)") (class "Default")
      (node (ref "U$1") (pin "P$26") (pinfunction "DISTRI_VBAT_P$26") (pintype "bidirectional"))
    )
    (net (code "62") (name "unconnected-(U$1-DISTRI_VBAT-PadP$28)") (class "Default")
      (node (ref "U$1") (pin "P$28") (pinfunction "DISTRI_VBAT_P$28") (pintype "bidirectional"))
    )
    (net (code "63") (name "unconnected-(U$1-DISTRI_VBAT-PadP$29)") (class "Default")
      (node (ref "U$1") (pin "P$29") (pinfunction "DISTRI_VBAT_P$29") (pintype "bidirectional"))
    )
    (net (code "64") (name "unconnected-(U$1-DISTRI_VBAT-PadP$31)") (class "Default")
      (node (ref "U$1") (pin "P$31") (pinfunction "DISTRI_VBAT_P$31") (pintype "bidirectional"))
    )
    (net (code "65") (name "unconnected-(U$1-ESTIMAT_GND-PadP$79)") (class "Default")
      (node (ref "U$1") (pin "P$79") (pinfunction "ESTIMAT_GND_P$79") (pintype "bidirectional"))
    )
    (net (code "66") (name "unconnected-(U$1-ESTIMAT_GND-PadP$80)") (class "Default")
      (node (ref "U$1") (pin "P$80") (pinfunction "ESTIMAT_GND_P$80") (pintype "bidirectional"))
    )
    (net (code "67") (name "unconnected-(U$1-ESTIMAT_VBAT-PadP$77)") (class "Default")
      (node (ref "U$1") (pin "P$77") (pinfunction "ESTIMAT_VBAT_P$77") (pintype "bidirectional"))
    )
    (net (code "68") (name "unconnected-(U$1-ESTIMAT_VBAT-PadP$78)") (class "Default")
      (node (ref "U$1") (pin "P$78") (pinfunction "ESTIMAT_VBAT_P$78") (pintype "bidirectional"))
    )
    (net (code "69") (name "unconnected-(U$1-GEN_VBATT$35-PadP$35)") (class "Default")
      (node (ref "U$1") (pin "P$35") (pinfunction "GEN_VBATT$35_P$35") (pintype "bidirectional"))
    )
    (net (code "70") (name "unconnected-(U$1-GEN_VBATT$36-PadP$36)") (class "Default")
      (node (ref "U$1") (pin "P$36") (pinfunction "GEN_VBATT$36_P$36") (pintype "bidirectional"))
    )
    (net (code "71") (name "unconnected-(U$1-P-PadP$59)") (class "Default")
      (node (ref "U$1") (pin "P$59") (pinfunction "P_P$59") (pintype "bidirectional"))
    )
    (net (code "72") (name "unconnected-(U$1-PPT_GND-PadP$1)") (class "Default")
      (node (ref "U$1") (pin "P$1") (pinfunction "PPT_GND_P$1") (pintype "bidirectional"))
    )
    (net (code "73") (name "unconnected-(U$1-PPT_GND-PadP$3)") (class "Default")
      (node (ref "U$1") (pin "P$3") (pinfunction "PPT_GND_P$3") (pintype "bidirectional"))
    )
    (net (code "74") (name "unconnected-(U$1-PPT_GND-PadP$6)") (class "Default")
      (node (ref "U$1") (pin "P$6") (pinfunction "PPT_GND_P$6") (pintype "bidirectional"))
    )
    (net (code "75") (name "unconnected-(U$1-PPT_GND-PadP$8)") (class "Default")
      (node (ref "U$1") (pin "P$8") (pinfunction "PPT_GND_P$8") (pintype "bidirectional"))
    )
    (net (code "76") (name "unconnected-(U$1-PPT_GND-PadP$9)") (class "Default")
      (node (ref "U$1") (pin "P$9") (pinfunction "PPT_GND_P$9") (pintype "bidirectional"))
    )
    (net (code "77") (name "unconnected-(U$1-PPT_GND-PadP$11)") (class "Default")
      (node (ref "U$1") (pin "P$11") (pinfunction "PPT_GND_P$11") (pintype "bidirectional"))
    )
    (net (code "78") (name "unconnected-(U$1-PPT_GND-PadP$14)") (class "Default")
      (node (ref "U$1") (pin "P$14") (pinfunction "PPT_GND_P$14") (pintype "bidirectional"))
    )
    (net (code "79") (name "unconnected-(U$1-PPT_GND-PadP$16)") (class "Default")
      (node (ref "U$1") (pin "P$16") (pinfunction "PPT_GND_P$16") (pintype "bidirectional"))
    )
    (net (code "80") (name "unconnected-(U$1-PPT_VBAT-PadP$2)") (class "Default")
      (node (ref "U$1") (pin "P$2") (pinfunction "PPT_VBAT_P$2") (pintype "bidirectional"))
    )
    (net (code "81") (name "unconnected-(U$1-PPT_VBAT-PadP$4)") (class "Default")
      (node (ref "U$1") (pin "P$4") (pinfunction "PPT_VBAT_P$4") (pintype "bidirectional"))
    )
    (net (code "82") (name "unconnected-(U$1-PPT_VBAT-PadP$5)") (class "Default")
      (node (ref "U$1") (pin "P$5") (pinfunction "PPT_VBAT_P$5") (pintype "bidirectional"))
    )
    (net (code "83") (name "unconnected-(U$1-PPT_VBAT-PadP$7)") (class "Default")
      (node (ref "U$1") (pin "P$7") (pinfunction "PPT_VBAT_P$7") (pintype "bidirectional"))
    )
    (net (code "84") (name "unconnected-(U$1-PPT_VBAT-PadP$10)") (class "Default")
      (node (ref "U$1") (pin "P$10") (pinfunction "PPT_VBAT_P$10") (pintype "bidirectional"))
    )
    (net (code "85") (name "unconnected-(U$1-PPT_VBAT-PadP$12)") (class "Default")
      (node (ref "U$1") (pin "P$12") (pinfunction "PPT_VBAT_P$12") (pintype "bidirectional"))
    )
    (net (code "86") (name "unconnected-(U$1-PPT_VBAT-PadP$13)") (class "Default")
      (node (ref "U$1") (pin "P$13") (pinfunction "PPT_VBAT_P$13") (pintype "bidirectional"))
    )
    (net (code "87") (name "unconnected-(U$1-PPT_VBAT-PadP$15)") (class "Default")
      (node (ref "U$1") (pin "P$15") (pinfunction "PPT_VBAT_P$15") (pintype "bidirectional"))
    )
    (net (code "88") (name "unconnected-(U$1-PadP$37)") (class "Default")
      (node (ref "U$1") (pin "P$37") (pinfunction "P$37_P$37") (pintype "bidirectional"))
    )
    (net (code "89") (name "unconnected-(U$1-PadP$38)") (class "Default")
      (node (ref "U$1") (pin "P$38") (pinfunction "P$38_P$38") (pintype "bidirectional"))
    )
    (net (code "90") (name "unconnected-(U$1-PadP$39)") (class "Default")
      (node (ref "U$1") (pin "P$39") (pinfunction "P$39_P$39") (pintype "bidirectional"))
    )
    (net (code "91") (name "unconnected-(U$1-PadP$40)") (class "Default")
      (node (ref "U$1") (pin "P$40") (pinfunction "P$40_P$40") (pintype "bidirectional"))
    )
    (net (code "92") (name "unconnected-(U$1-PadP$41)") (class "Default")
      (node (ref "U$1") (pin "P$41") (pinfunction "P$41_P$41") (pintype "bidirectional"))
    )
    (net (code "93") (name "unconnected-(U$1-PadP$42)") (class "Default")
      (node (ref "U$1") (pin "P$42") (pinfunction "P$42_P$42") (pintype "bidirectional"))
    )
    (net (code "94") (name "unconnected-(U$1-PadP$43)") (class "Default")
      (node (ref "U$1") (pin "P$43") (pinfunction "P$43_P$43") (pintype "bidirectional"))
    )
    (net (code "95") (name "unconnected-(U$1-PadP$44)") (class "Default")
      (node (ref "U$1") (pin "P$44") (pinfunction "P$44_P$44") (pintype "bidirectional"))
    )
    (net (code "96") (name "unconnected-(U$1-PadP$46)") (class "Default")
      (node (ref "U$1") (pin "P$46") (pinfunction "P$46_P$46") (pintype "bidirectional"))
    )
    (net (code "97") (name "unconnected-(U$1-PadP$47)") (class "Default")
      (node (ref "U$1") (pin "P$47") (pinfunction "P$47_P$47") (pintype "bidirectional"))
    )
    (net (code "98") (name "unconnected-(U$1-PadP$48)") (class "Default")
      (node (ref "U$1") (pin "P$48") (pinfunction "P$48_P$48") (pintype "bidirectional"))
    )
    (net (code "99") (name "unconnected-(U$1-PadP$50)") (class "Default")
      (node (ref "U$1") (pin "P$50") (pinfunction "P$50_P$50") (pintype "bidirectional"))
    )
    (net (code "100") (name "unconnected-(U$1-PadP$54)") (class "Default")
      (node (ref "U$1") (pin "P$54") (pinfunction "P$54_P$54") (pintype "bidirectional"))
    )
    (net (code "101") (name "unconnected-(U$1-PadP$58)") (class "Default")
      (node (ref "U$1") (pin "P$58") (pinfunction "P$58_P$58") (pintype "bidirectional"))
    )
    (net (code "102") (name "unconnected-(U$1-PadP$60)") (class "Default")
      (node (ref "U$1") (pin "P$60") (pinfunction "P$60_P$60") (pintype "bidirectional"))
    )
    (net (code "103") (name "unconnected-(U$1-PadP$61)") (class "Default")
      (node (ref "U$1") (pin "P$61") (pinfunction "P$61_P$61") (pintype "bidirectional"))
    )
    (net (code "104") (name "unconnected-(U$1-PadP$62)") (class "Default")
      (node (ref "U$1") (pin "P$62") (pinfunction "P$62_P$62") (pintype "bidirectional"))
    )
    (net (code "105") (name "unconnected-(U$1-PadP$63)") (class "Default")
      (node (ref "U$1") (pin "P$63") (pinfunction "P$63_P$63") (pintype "bidirectional"))
    )
    (net (code "106") (name "unconnected-(U$1-PadP$64)") (class "Default")
      (node (ref "U$1") (pin "P$64") (pinfunction "P$64_P$64") (pintype "bidirectional"))
    )
    (net (code "107") (name "unconnected-(U$1-PadP$65)") (class "Default")
      (node (ref "U$1") (pin "P$65") (pinfunction "P$65_P$65") (pintype "bidirectional"))
    )
    (net (code "108") (name "unconnected-(U$1-PadP$66)") (class "Default")
      (node (ref "U$1") (pin "P$66") (pinfunction "P$66_P$66") (pintype "bidirectional"))
    )
    (net (code "109") (name "unconnected-(U$1-PadP$67)") (class "Default")
      (node (ref "U$1") (pin "P$67") (pinfunction "P$67_P$67") (pintype "bidirectional"))
    )
    (net (code "110") (name "unconnected-(U$1-PadP$68)") (class "Default")
      (node (ref "U$1") (pin "P$68") (pinfunction "P$68_P$68") (pintype "bidirectional"))
    )
    (net (code "111") (name "unconnected-(U$1-PadP$73)") (class "Default")
      (node (ref "U$1") (pin "P$73") (pinfunction "P$73_P$73") (pintype "bidirectional"))
    )
    (net (code "112") (name "unconnected-(U$1-PadP$74)") (class "Default")
      (node (ref "U$1") (pin "P$74") (pinfunction "P$74_P$74") (pintype "bidirectional"))
    )
    (net (code "113") (name "unconnected-(U$1-PadP$75)") (class "Default")
      (node (ref "U$1") (pin "P$75") (pinfunction "P$75_P$75") (pintype "bidirectional"))
    )
    (net (code "114") (name "unconnected-(U$1-PadP$76)") (class "Default")
      (node (ref "U$1") (pin "P$76") (pinfunction "P$76_P$76") (pintype "bidirectional"))
    )
    (net (code "115") (name "unconnected-(U$1-PadP$81)") (class "Default")
      (node (ref "U$1") (pin "P$81") (pinfunction "P$81_P$81") (pintype "bidirectional"))
    )
    (net (code "116") (name "unconnected-(U$1-PadP$82)") (class "Default")
      (node (ref "U$1") (pin "P$82") (pinfunction "P$82_P$82") (pintype "bidirectional"))
    )
    (net (code "117") (name "unconnected-(U$1-PadP$83)") (class "Default")
      (node (ref "U$1") (pin "P$83") (pinfunction "P$83_P$83") (pintype "bidirectional"))
    )
    (net (code "118") (name "unconnected-(U$1-PadP$84)") (class "Default")
      (node (ref "U$1") (pin "P$84") (pinfunction "P$84_P$84") (pintype "bidirectional"))
    )
    (net (code "119") (name "unconnected-(U$1-PadP$89)") (class "Default")
      (node (ref "U$1") (pin "P$89") (pinfunction "P$89_P$89") (pintype "bidirectional"))
    )
    (net (code "120") (name "unconnected-(U$1-PadP$90)") (class "Default")
      (node (ref "U$1") (pin "P$90") (pinfunction "P$90_P$90") (pintype "bidirectional"))
    )
    (net (code "121") (name "unconnected-(U$1-PadP$91)") (class "Default")
      (node (ref "U$1") (pin "P$91") (pinfunction "P$91_P$91") (pintype "bidirectional"))
    )
    (net (code "122") (name "unconnected-(U$1-PadP$92)") (class "Default")
      (node (ref "U$1") (pin "P$92") (pinfunction "P$92_P$92") (pintype "bidirectional"))
    )
    (net (code "123") (name "unconnected-(U$1-PadP$95)") (class "Default")
      (node (ref "U$1") (pin "P$95") (pinfunction "P$95_P$95") (pintype "bidirectional"))
    )
    (net (code "124") (name "unconnected-(U$1-PadP$96)") (class "Default")
      (node (ref "U$1") (pin "P$96") (pinfunction "P$96_P$96") (pintype "bidirectional"))
    )
    (net (code "125") (name "unconnected-(U$1-RAHS_GND-PadP$94)") (class "Default")
      (node (ref "U$1") (pin "P$94") (pinfunction "RAHS_GND_P$94") (pintype "bidirectional"))
    )
    (net (code "126") (name "unconnected-(U$1-RAHS_VBAT-PadP$93)") (class "Default")
      (node (ref "U$1") (pin "P$93") (pinfunction "RAHS_VBAT_P$93") (pintype "bidirectional"))
    )
    (net (code "127") (name "unconnected-(U$1-TOPDEPLOY+-PadP$51)") (class "Default")
      (node (ref "U$1") (pin "P$51") (pinfunction "TOPDEPLOY+_P$51") (pintype "bidirectional"))
    )
    (net (code "128") (name "unconnected-(U$1-TOPDEPLOY+-PadP$55)") (class "Default")
      (node (ref "U$1") (pin "P$55") (pinfunction "TOPDEPLOY+_P$55") (pintype "bidirectional"))
    )
    (net (code "129") (name "unconnected-(U$1-TOPDEPLOY-$52-PadP$52)") (class "Default")
      (node (ref "U$1") (pin "P$52") (pinfunction "TOPDEPLOY-$52_P$52") (pintype "bidirectional"))
    )
    (net (code "130") (name "unconnected-(U$1-TOPDEPLOY-$56-PadP$56)") (class "Default")
      (node (ref "U$1") (pin "P$56") (pinfunction "TOPDEPLOY-$56_P$56") (pintype "bidirectional"))
    )
    (net (code "131") (name "unconnected-(U$1-WHEEL_GND-PadP$71)") (class "Default")
      (node (ref "U$1") (pin "P$71") (pinfunction "WHEEL_GND_P$71") (pintype "bidirectional"))
    )
    (net (code "132") (name "unconnected-(U$1-WHEEL_GND-PadP$72)") (class "Default")
      (node (ref "U$1") (pin "P$72") (pinfunction "WHEEL_GND_P$72") (pintype "bidirectional"))
    )
    (net (code "133") (name "unconnected-(U$1-WHEEL_VBAT-PadP$69)") (class "Default")
      (node (ref "U$1") (pin "P$69") (pinfunction "WHEEL_VBAT_P$69") (pintype "bidirectional"))
    )
    (net (code "134") (name "unconnected-(U$1-WHEEL_VBAT-PadP$70)") (class "Default")
      (node (ref "U$1") (pin "P$70") (pinfunction "WHEEL_VBAT_P$70") (pintype "bidirectional"))
    )
    (net (code "135") (name "unconnected-(U$7-P2.3_SPI-CS2-PadP2.4_SPI-CS2)") (class "Default")
      (node (ref "U$7") (pin "P2.4_SPI-CS2") (pinfunction "P2.3_SPI-CS2_P2.4_SPI-CS2") (pintype "bidirectional"))
    )
    (net (code "136") (name "unconnected-(U$7-PadP1.0_A0)") (class "Default")
      (node (ref "U$7") (pin "P1.0_A0") (pinfunction "P1.0_A0_P1.0_A0") (pintype "bidirectional"))
    )
    (net (code "137") (name "unconnected-(U$7-PadP1.1_A1)") (class "Default")
      (node (ref "U$7") (pin "P1.1_A1") (pinfunction "P1.1_A1_P1.1_A1") (pintype "bidirectional"))
    )
    (net (code "138") (name "unconnected-(U$7-PadP1.2_A2)") (class "Default")
      (node (ref "U$7") (pin "P1.2_A2") (pinfunction "P1.2_A2_P1.2_A2") (pintype "bidirectional"))
    )
    (net (code "139") (name "unconnected-(U$7-PadP1.3_A3)") (class "Default")
      (node (ref "U$7") (pin "P1.3_A3") (pinfunction "P1.3_A3_P1.3_A3") (pintype "bidirectional"))
    )
    (net (code "140") (name "unconnected-(U$7-PadP1.4_A4)") (class "Default")
      (node (ref "U$7") (pin "P1.4_A4") (pinfunction "P1.4_A4_P1.4_A4") (pintype "bidirectional"))
    )
    (net (code "141") (name "unconnected-(U$7-PadP1.5_A5)") (class "Default")
      (node (ref "U$7") (pin "P1.5_A5") (pinfunction "P1.5_A5_P1.5_A5") (pintype "bidirectional"))
    )
    (net (code "142") (name "unconnected-(U$7-PadP2.5_GPIO)") (class "Default")
      (node (ref "U$7") (pin "P2.5_GPIO") (pinfunction "P2.5_GPIO_P2.5_GPIO") (pintype "bidirectional"))
    )
    (net (code "143") (name "unconnected-(U$7-PadP2.7_SPI-CS3)") (class "Default")
      (node (ref "U$7") (pin "P2.7_SPI-CS3") (pinfunction "P2.7_SPI-CS3_P2.7_SPI-CS3") (pintype "bidirectional"))
    )
    (net (code "144") (name "unconnected-(U$7-PadP3.0_A12)") (class "Default")
      (node (ref "U$7") (pin "P3.0_A12") (pinfunction "P3.0_A12_P3.0_A12") (pintype "bidirectional"))
    )
    (net (code "145") (name "unconnected-(U$7-PadP3.1_A13)") (class "Default")
      (node (ref "U$7") (pin "P3.1_A13") (pinfunction "P3.1_A13_P3.1_A13") (pintype "bidirectional"))
    )
    (net (code "146") (name "unconnected-(U$7-PadP3.2_A14)") (class "Default")
      (node (ref "U$7") (pin "P3.2_A14") (pinfunction "P3.2_A14_P3.2_A14") (pintype "bidirectional"))
    )
    (net (code "147") (name "unconnected-(U$7-PadP3.3_A15)") (class "Default")
      (node (ref "U$7") (pin "P3.3_A15") (pinfunction "P3.3_A15_P3.3_A15") (pintype "bidirectional"))
    )
    (net (code "148") (name "unconnected-(U$7-PadP4.0_GPIO)") (class "Default")
      (node (ref "U$7") (pin "P4.0_GPIO") (pinfunction "P4.0_GPIO_P4.0_GPIO") (pintype "bidirectional"))
    )
    (net (code "149") (name "unconnected-(U$7-PadP4.1_GPIO)") (class "Default")
      (node (ref "U$7") (pin "P4.1_GPIO") (pinfunction "P4.1_GPIO_P4.1_GPIO") (pintype "bidirectional"))
    )
    (net (code "150") (name "unconnected-(U$7-PadP4.2_GPIO)") (class "Default")
      (node (ref "U$7") (pin "P4.2_GPIO") (pinfunction "P4.2_GPIO_P4.2_GPIO") (pintype "bidirectional"))
    )
    (net (code "151") (name "unconnected-(U$7-PadP4.3_GPIO)") (class "Default")
      (node (ref "U$7") (pin "P4.3_GPIO") (pinfunction "P4.3_GPIO_P4.3_GPIO") (pintype "bidirectional"))
    )
    (net (code "152") (name "unconnected-(U$7-PadP5.0_I2C-SDA-1)") (class "Default")
      (node (ref "U$7") (pin "P5.0_I2C-SDA-1") (pinfunction "P5.0_I2C-SDA-1_P5.0_I2C-SDA-1") (pintype "bidirectional"))
    )
    (net (code "153") (name "unconnected-(U$7-PadP5.1_I2C-SCL-1)") (class "Default")
      (node (ref "U$7") (pin "P5.1_I2C-SCL-1") (pinfunction "P5.1_I2C-SCL-1_P5.1_I2C-SCL-1") (pintype "bidirectional"))
    )
    (net (code "154") (name "unconnected-(U$7-PadP5.4_SPI-MOSI)") (class "Default")
      (node (ref "U$7") (pin "P5.4_SPI-MOSI") (pinfunction "P5.4_SPI-MOSI_P5.4_SPI-MOSI") (pintype "bidirectional"))
    )
    (net (code "155") (name "unconnected-(U$7-PadP5.5_SPI-MISO)") (class "Default")
      (node (ref "U$7") (pin "P5.5_SPI-MISO") (pinfunction "P5.5_SPI-MISO_P5.5_SPI-MISO") (pintype "bidirectional"))
    )
    (net (code "156") (name "unconnected-(U$7-PadP5.6_SPI-CLK)") (class "Default")
      (node (ref "U$7") (pin "P5.6_SPI-CLK") (pinfunction "P5.6_SPI-CLK_P5.6_SPI-CLK") (pintype "bidirectional"))
    )
    (net (code "157") (name "unconnected-(U$7-PadP7.0_I2C-SDA-2)") (class "Default")
      (node (ref "U$7") (pin "P7.0_I2C-SDA-2") (pinfunction "P7.0_I2C-SDA-2_P7.0_I2C-SDA-2") (pintype "bidirectional"))
    )
    (net (code "158") (name "unconnected-(U$7-PadP7.1_I2C-SCL-2)") (class "Default")
      (node (ref "U$7") (pin "P7.1_I2C-SCL-2") (pinfunction "P7.1_I2C-SCL-2_P7.1_I2C-SCL-2") (pintype "bidirectional"))
    )
    (net (code "159") (name "unconnected-(U$7-PadP7.3_GPIO)") (class "Default")
      (node (ref "U$7") (pin "P7.3_GPIO") (pinfunction "P7.3_GPIO_P7.3_GPIO") (pintype "bidirectional"))
    )
    (net (code "160") (name "unconnected-(U$7-PadP7.4_GPIO)") (class "Default")
      (node (ref "U$7") (pin "P7.4_GPIO") (pinfunction "P7.4_GPIO_P7.4_GPIO") (pintype "bidirectional"))
    )
    (net (code "161") (name "unconnected-(U$9-NC-PadP$2)") (class "Default")
      (node (ref "U$9") (pin "P$2") (pinfunction "NC_P$2") (pintype "bidirectional"))
    )
  )
)
